# display.net
KiCad netlist of a schematic drawn in Altium Designer
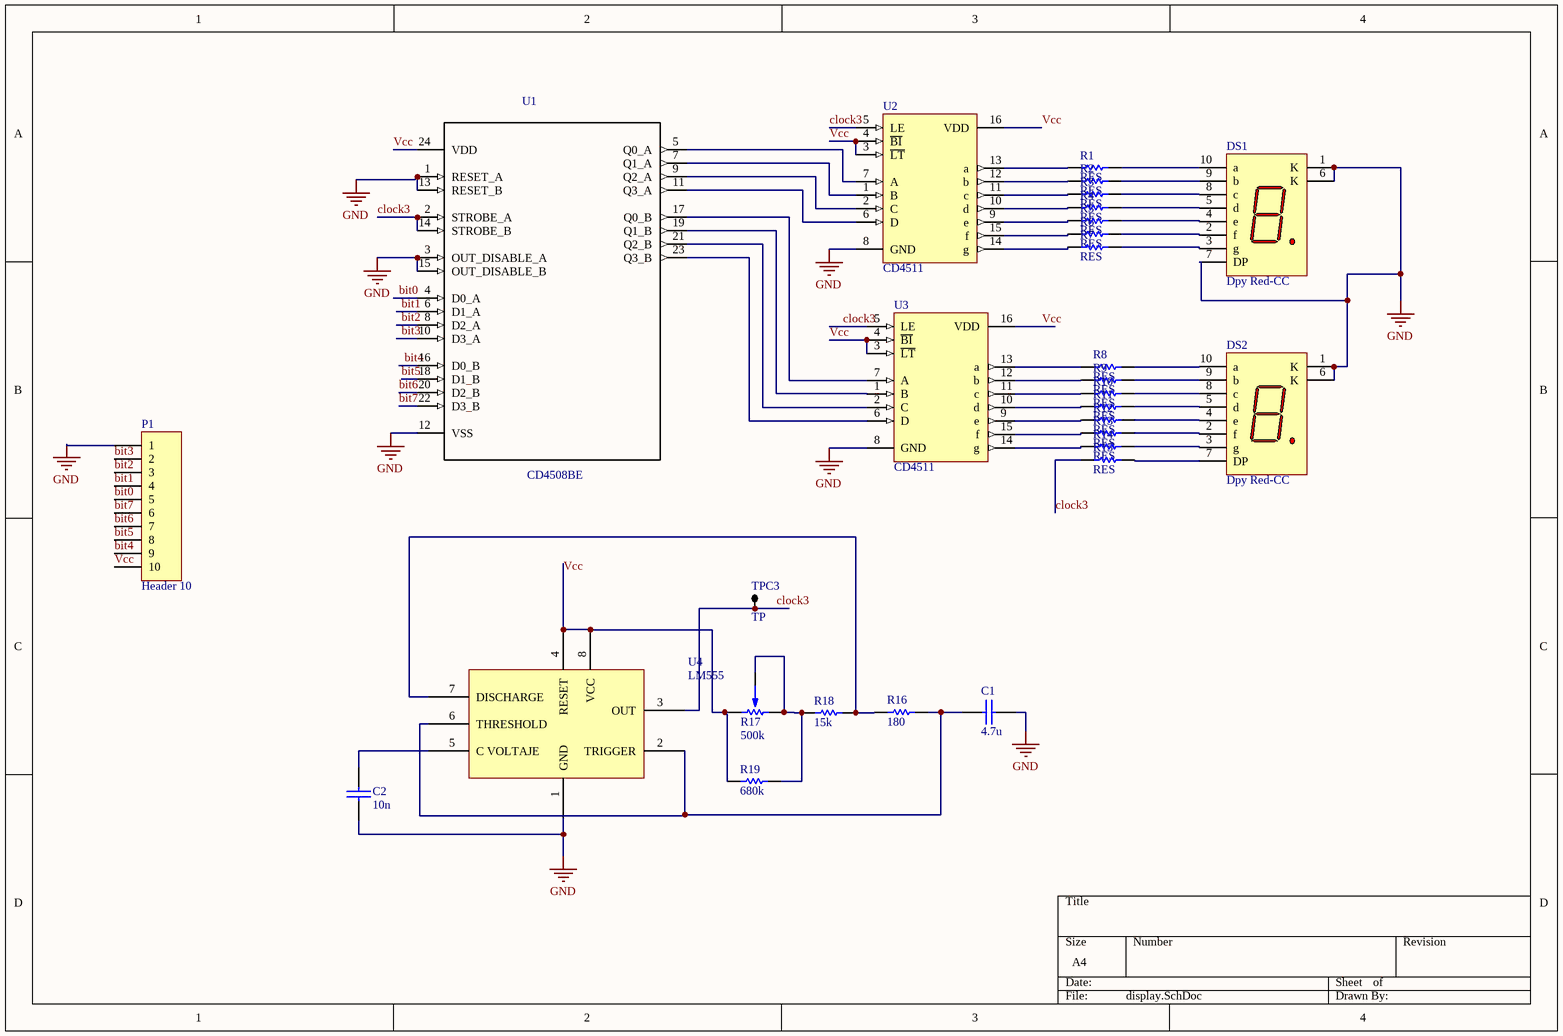
[diagram p0: display.SchDoc]

(export (version "E")
  (design (tool "Eeschema 10.0.6"))
  (components
    (comp (ref "C1") (value "4.7u") (footprint "0805") (libsource (lib "LIBEBAL") (part "CAP")))
    (comp (ref "C2") (value "10n") (footprint "CAP200") (libsource (lib "LIBEBAL") (part "CAP")))
    (comp (ref "DS1")
      (value "Dpy Red-CC")
      (footprint "A")
      (description "7.62 mm Black Surface HER 7-Segment Display: CC, RH DP")
      (fields (field (name "PUBLISHER") "Altium Limited"))
      (libsource (lib "Miscellaneous Devices") (part "Dpy Red-CC"))
    )
    (comp (ref "DS2")
      (value "Dpy Red-CC")
      (footprint "A")
      (description "7.62 mm Black Surface HER 7-Segment Display: CC, RH DP")
      (fields (field (name "PUBLISHER") "Altium Limited"))
      (libsource (lib "Miscellaneous Devices") (part "Dpy Red-CC"))
    )
    (comp (ref "P1")
      (value "Header 10")
      (footprint "HDR1X10")
      (description "Header, 10-Pin")
      (fields (field (name "PUBLISHER") "Altium Limited"))
      (libsource (lib "Miscellaneous Connectors") (part "Header 10"))
    )
    (comp (ref "R1") (value "RES") (footprint "0805") (libsource (lib "LIBEBAL") (part "RES")))
    (comp (ref "R2") (value "RES") (footprint "0805") (libsource (lib "LIBEBAL") (part "RES")))
    (comp (ref "R3") (value "RES") (footprint "0805") (libsource (lib "LIBEBAL") (part "RES")))
    (comp (ref "R4") (value "RES") (footprint "0805") (libsource (lib "LIBEBAL") (part "RES")))
    (comp (ref "R5") (value "RES") (footprint "0805") (libsource (lib "LIBEBAL") (part "RES")))
    (comp (ref "R6") (value "RES") (footprint "0805") (libsource (lib "LIBEBAL") (part "RES")))
    (comp (ref "R7") (value "RES") (footprint "0805") (libsource (lib "LIBEBAL") (part "RES")))
    (comp (ref "R8") (value "RES") (footprint "0805") (libsource (lib "LIBEBAL") (part "RES")))
    (comp (ref "R9") (value "RES") (footprint "0805") (libsource (lib "LIBEBAL") (part "RES")))
    (comp (ref "R10") (value "RES") (footprint "0805") (libsource (lib "LIBEBAL") (part "RES")))
    (comp (ref "R11") (value "RES") (footprint "0805") (libsource (lib "LIBEBAL") (part "RES")))
    (comp (ref "R12") (value "RES") (footprint "0805") (libsource (lib "LIBEBAL") (part "RES")))
    (comp (ref "R13") (value "RES") (footprint "0805") (libsource (lib "LIBEBAL") (part "RES")))
    (comp (ref "R14") (value "RES") (footprint "0805") (libsource (lib "LIBEBAL") (part "RES")))
    (comp (ref "R15") (value "RES") (footprint "0805") (libsource (lib "LIBEBAL") (part "RES")))
    (comp (ref "R16") (value "180") (footprint "0805") (libsource (lib "LIBEBAL") (part "RES")))
    (comp (ref "R17")
      (value "500k")
      (footprint "POTENCIOMETRO")
      (libsource (lib "LIBEBAL") (part "POTENCIOMETRO"))
    )
    (comp (ref "R18") (value "15k") (footprint "0805") (libsource (lib "LIBEBAL") (part "RES")))
    (comp (ref "R19") (value "680k") (footprint "RES400") (libsource (lib "LIBEBAL") (part "RES")))
    (comp (ref "TPC3") (value "TP") (footprint "TPTH") (libsource (lib "LIBEBAL") (part "TP")))
    (comp (ref "U1")
      (value "CD4508BE")
      (footprint "*DIP254P1080X508-24")
      (description "Latch Transparent 3-ST 8-CH D-Type 24-Pin PDIP")
      (fields (field (name "MF") "Texas Instruments"))
      (libsource (lib "CD4508BE") (part "CD4508BE"))
    )
    (comp (ref "U2")
      (value "CD4511")
      (footprint "DIP16")
      (description "BCD to 7 SEGMENTOS")
      (libsource (lib "LIBEBAL") (part "CD4511"))
    )
    (comp (ref "U3")
      (value "CD4511")
      (footprint "DIP16")
      (description "BCD to 7 SEGMENTOS")
      (libsource (lib "LIBEBAL") (part "CD4511"))
    )
    (comp (ref "U4")
      (value "LM555")
      (footprint "DIP8")
      (description "Timer")
      (libsource (lib "LIBEBAL") (part "LM555"))
    )
  )
  (nets
    (net (code "1") (name "/Vcc") (class "Default")
      (node (ref "P1") (pin "10") (pinfunction "10_10") (pintype "passive"))
      (node (ref "R17") (pin "1") (pinfunction "1_1") (pintype "passive"))
      (node (ref "R19") (pin "1") (pinfunction "1_1") (pintype "passive"))
      (node (ref "U1") (pin "24") (pinfunction "VDD_24") (pintype "power_in"))
      (node (ref "U2") (pin "16") (pinfunction "VDD_16") (pintype "power_in"))
      (node (ref "U2") (pin "3") (pinfunction "~{LT}_3") (pintype "input"))
      (node (ref "U2") (pin "4") (pinfunction "~{BI}_4") (pintype "input"))
      (node (ref "U3") (pin "16") (pinfunction "VDD_16") (pintype "power_in"))
      (node (ref "U3") (pin "3") (pinfunction "~{LT}_3") (pintype "input"))
      (node (ref "U3") (pin "4") (pinfunction "~{BI}_4") (pintype "input"))
      (node (ref "U4") (pin "4") (pinfunction "RESET_4") (pintype "passive"))
      (node (ref "U4") (pin "8") (pinfunction "VCC_8") (pintype "passive"))
    )
    (net (code "2") (name "/bit0") (class "Default")
      (node (ref "P1") (pin "5") (pinfunction "5_5") (pintype "passive"))
      (node (ref "U1") (pin "4") (pinfunction "D0_A_4") (pintype "input"))
    )
    (net (code "3") (name "/bit1") (class "Default")
      (node (ref "P1") (pin "4") (pinfunction "4_4") (pintype "passive"))
      (node (ref "U1") (pin "6") (pinfunction "D1_A_6") (pintype "input"))
    )
    (net (code "4") (name "/bit2") (class "Default")
      (node (ref "P1") (pin "3") (pinfunction "3_3") (pintype "passive"))
      (node (ref "U1") (pin "8") (pinfunction "D2_A_8") (pintype "input"))
    )
    (net (code "5") (name "/bit3") (class "Default")
      (node (ref "P1") (pin "2") (pinfunction "2_2") (pintype "passive"))
      (node (ref "U1") (pin "10") (pinfunction "D3_A_10") (pintype "input"))
    )
    (net (code "6") (name "/bit4") (class "Default")
      (node (ref "P1") (pin "9") (pinfunction "9_9") (pintype "passive"))
      (node (ref "U1") (pin "16") (pinfunction "D0_B_16") (pintype "input"))
    )
    (net (code "7") (name "/bit5") (class "Default")
      (node (ref "P1") (pin "8") (pinfunction "8_8") (pintype "passive"))
      (node (ref "U1") (pin "18") (pinfunction "D1_B_18") (pintype "input"))
    )
    (net (code "8") (name "/bit6") (class "Default")
      (node (ref "P1") (pin "7") (pinfunction "7_7") (pintype "passive"))
      (node (ref "U1") (pin "20") (pinfunction "D2_B_20") (pintype "input"))
    )
    (net (code "9") (name "/bit7") (class "Default")
      (node (ref "P1") (pin "6") (pinfunction "6_6") (pintype "passive"))
      (node (ref "U1") (pin "22") (pinfunction "D3_B_22") (pintype "input"))
    )
    (net (code "10") (name "/clock3") (class "Default")
      (node (ref "R15") (pin "1") (pinfunction "1_1") (pintype "passive"))
      (node (ref "TPC3") (pin "1") (pinfunction "1_1") (pintype "passive"))
      (node (ref "U1") (pin "14") (pinfunction "STROBE_B_14") (pintype "input"))
      (node (ref "U1") (pin "2") (pinfunction "STROBE_A_2") (pintype "input"))
      (node (ref "U2") (pin "5") (pinfunction "LE_5") (pintype "input"))
      (node (ref "U3") (pin "5") (pinfunction "LE_5") (pintype "input"))
      (node (ref "U4") (pin "3") (pinfunction "OUT_3") (pintype "passive"))
    )
    (net (code "11") (name "GND") (class "Default")
      (node (ref "C1") (pin "2") (pinfunction "2_2") (pintype "passive"))
      (node (ref "C2") (pin "1") (pinfunction "1_1") (pintype "passive"))
      (node (ref "DS1") (pin "1") (pinfunction "K_1") (pintype "passive"))
      (node (ref "DS1") (pin "6") (pinfunction "K_6") (pintype "passive"))
      (node (ref "DS1") (pin "7") (pinfunction "DP_7") (pintype "passive"))
      (node (ref "DS2") (pin "1") (pinfunction "K_1") (pintype "passive"))
      (node (ref "DS2") (pin "6") (pinfunction "K_6") (pintype "passive"))
      (node (ref "P1") (pin "1") (pinfunction "1_1") (pintype "passive"))
      (node (ref "U1") (pin "1") (pinfunction "RESET_A_1") (pintype "input"))
      (node (ref "U1") (pin "12") (pinfunction "VSS_12") (pintype "power_in"))
      (node (ref "U1") (pin "13") (pinfunction "RESET_B_13") (pintype "input"))
      (node (ref "U1") (pin "15") (pinfunction "OUT_DISABLE_B_15") (pintype "input"))
      (node (ref "U1") (pin "3") (pinfunction "OUT_DISABLE_A_3") (pintype "input"))
      (node (ref "U2") (pin "8") (pinfunction "GND_8") (pintype "power_in"))
      (node (ref "U3") (pin "8") (pinfunction "GND_8") (pintype "power_in"))
      (node (ref "U4") (pin "1") (pinfunction "GND_1") (pintype "passive"))
    )
    (net (code "12") (name "Net-(DS1-a)") (class "Default")
      (node (ref "DS1") (pin "10") (pinfunction "a_10") (pintype "passive"))
      (node (ref "R1") (pin "2") (pinfunction "2_2") (pintype "passive"))
    )
    (net (code "13") (name "Net-(DS1-b)") (class "Default")
      (node (ref "DS1") (pin "9") (pinfunction "b_9") (pintype "passive"))
      (node (ref "R2") (pin "2") (pinfunction "2_2") (pintype "passive"))
    )
    (net (code "14") (name "Net-(DS1-c)") (class "Default")
      (node (ref "DS1") (pin "8") (pinfunction "c_8") (pintype "passive"))
      (node (ref "R3") (pin "2") (pinfunction "2_2") (pintype "passive"))
    )
    (net (code "15") (name "Net-(DS1-d)") (class "Default")
      (node (ref "DS1") (pin "5") (pinfunction "d_5") (pintype "passive"))
      (node (ref "R4") (pin "2") (pinfunction "2_2") (pintype "passive"))
    )
    (net (code "16") (name "Net-(DS1-e)") (class "Default")
      (node (ref "DS1") (pin "4") (pinfunction "e_4") (pintype "passive"))
      (node (ref "R5") (pin "2") (pinfunction "2_2") (pintype "passive"))
    )
    (net (code "17") (name "Net-(DS1-f)") (class "Default")
      (node (ref "DS1") (pin "2") (pinfunction "f_2") (pintype "passive"))
      (node (ref "R6") (pin "2") (pinfunction "2_2") (pintype "passive"))
    )
    (net (code "18") (name "Net-(DS1-g)") (class "Default")
      (node (ref "DS1") (pin "3") (pinfunction "g_3") (pintype "passive"))
      (node (ref "R7") (pin "2") (pinfunction "2_2") (pintype "passive"))
    )
    (net (code "19") (name "Net-(DS2-DP)") (class "Default")
      (node (ref "DS2") (pin "7") (pinfunction "DP_7") (pintype "passive"))
      (node (ref "R15") (pin "2") (pinfunction "2_2") (pintype "passive"))
    )
    (net (code "20") (name "Net-(DS2-a)") (class "Default")
      (node (ref "DS2") (pin "10") (pinfunction "a_10") (pintype "passive"))
      (node (ref "R8") (pin "2") (pinfunction "2_2") (pintype "passive"))
    )
    (net (code "21") (name "Net-(DS2-b)") (class "Default")
      (node (ref "DS2") (pin "9") (pinfunction "b_9") (pintype "passive"))
      (node (ref "R9") (pin "2") (pinfunction "2_2") (pintype "passive"))
    )
    (net (code "22") (name "Net-(DS2-c)") (class "Default")
      (node (ref "DS2") (pin "8") (pinfunction "c_8") (pintype "passive"))
      (node (ref "R10") (pin "2") (pinfunction "2_2") (pintype "passive"))
    )
    (net (code "23") (name "Net-(DS2-d)") (class "Default")
      (node (ref "DS2") (pin "5") (pinfunction "d_5") (pintype "passive"))
      (node (ref "R11") (pin "2") (pinfunction "2_2") (pintype "passive"))
    )
    (net (code "24") (name "Net-(DS2-e)") (class "Default")
      (node (ref "DS2") (pin "4") (pinfunction "e_4") (pintype "passive"))
      (node (ref "R12") (pin "2") (pinfunction "2_2") (pintype "passive"))
    )
    (net (code "25") (name "Net-(DS2-f)") (class "Default")
      (node (ref "DS2") (pin "2") (pinfunction "f_2") (pintype "passive"))
      (node (ref "R13") (pin "2") (pinfunction "2_2") (pintype "passive"))
    )
    (net (code "26") (name "Net-(DS2-g)") (class "Default")
      (node (ref "DS2") (pin "3") (pinfunction "g_3") (pintype "passive"))
      (node (ref "R14") (pin "2") (pinfunction "2_2") (pintype "passive"))
    )
    (net (code "27") (name "Net-(R17-Pad2)") (class "Default")
      (node (ref "R17") (pin "2") (pinfunction "2_2") (pintype "passive"))
      (node (ref "R17") (pin "3") (pinfunction "3_3") (pintype "passive"))
      (node (ref "R18") (pin "1") (pinfunction "1_1") (pintype "passive"))
      (node (ref "R19") (pin "2") (pinfunction "2_2") (pintype "passive"))
    )
    (net (code "28") (name "Net-(U1-Q0_A)") (class "Default")
      (node (ref "U1") (pin "5") (pinfunction "Q0_A_5") (pintype "output"))
      (node (ref "U2") (pin "7") (pinfunction "A_7") (pintype "input"))
    )
    (net (code "29") (name "Net-(U1-Q0_B)") (class "Default")
      (node (ref "U1") (pin "17") (pinfunction "Q0_B_17") (pintype "output"))
      (node (ref "U3") (pin "7") (pinfunction "A_7") (pintype "input"))
    )
    (net (code "30") (name "Net-(U1-Q1_A)") (class "Default")
      (node (ref "U1") (pin "7") (pinfunction "Q1_A_7") (pintype "output"))
      (node (ref "U2") (pin "1") (pinfunction "B_1") (pintype "input"))
    )
    (net (code "31") (name "Net-(U1-Q1_B)") (class "Default")
      (node (ref "U1") (pin "19") (pinfunction "Q1_B_19") (pintype "output"))
      (node (ref "U3") (pin "1") (pinfunction "B_1") (pintype "input"))
    )
    (net (code "32") (name "Net-(U1-Q2_A)") (class "Default")
      (node (ref "U1") (pin "9") (pinfunction "Q2_A_9") (pintype "output"))
      (node (ref "U2") (pin "2") (pinfunction "C_2") (pintype "input"))
    )
    (net (code "33") (name "Net-(U1-Q2_B)") (class "Default")
      (node (ref "U1") (pin "21") (pinfunction "Q2_B_21") (pintype "output"))
      (node (ref "U3") (pin "2") (pinfunction "C_2") (pintype "input"))
    )
    (net (code "34") (name "Net-(U1-Q3_A)") (class "Default")
      (node (ref "U1") (pin "11") (pinfunction "Q3_A_11") (pintype "output"))
      (node (ref "U2") (pin "6") (pinfunction "D_6") (pintype "input"))
    )
    (net (code "35") (name "Net-(U1-Q3_B)") (class "Default")
      (node (ref "U1") (pin "23") (pinfunction "Q3_B_23") (pintype "output"))
      (node (ref "U3") (pin "6") (pinfunction "D_6") (pintype "input"))
    )
    (net (code "36") (name "Net-(U2-a)") (class "Default")
      (node (ref "R1") (pin "1") (pinfunction "1_1") (pintype "passive"))
      (node (ref "U2") (pin "13") (pinfunction "a_13") (pintype "output"))
    )
    (net (code "37") (name "Net-(U2-b)") (class "Default")
      (node (ref "R2") (pin "1") (pinfunction "1_1") (pintype "passive"))
      (node (ref "U2") (pin "12") (pinfunction "b_12") (pintype "output"))
    )
    (net (code "38") (name "Net-(U2-c)") (class "Default")
      (node (ref "R3") (pin "1") (pinfunction "1_1") (pintype "passive"))
      (node (ref "U2") (pin "11") (pinfunction "c_11") (pintype "output"))
    )
    (net (code "39") (name "Net-(U2-d)") (class "Default")
      (node (ref "R4") (pin "1") (pinfunction "1_1") (pintype "passive"))
      (node (ref "U2") (pin "10") (pinfunction "d_10") (pintype "output"))
    )
    (net (code "40") (name "Net-(U2-e)") (class "Default")
      (node (ref "R5") (pin "1") (pinfunction "1_1") (pintype "passive"))
      (node (ref "U2") (pin "9") (pinfunction "e_9") (pintype "output"))
    )
    (net (code "41") (name "Net-(U2-f)") (class "Default")
      (node (ref "R6") (pin "1") (pinfunction "1_1") (pintype "passive"))
      (node (ref "U2") (pin "15") (pinfunction "f_15") (pintype "output"))
    )
    (net (code "42") (name "Net-(U2-g)") (class "Default")
      (node (ref "R7") (pin "1") (pinfunction "1_1") (pintype "passive"))
      (node (ref "U2") (pin "14") (pinfunction "g_14") (pintype "output"))
    )
    (net (code "43") (name "Net-(U3-a)") (class "Default")
      (node (ref "R8") (pin "1") (pinfunction "1_1") (pintype "passive"))
      (node (ref "U3") (pin "13") (pinfunction "a_13") (pintype "output"))
    )
    (net (code "44") (name "Net-(U3-b)") (class "Default")
      (node (ref "R9") (pin "1") (pinfunction "1_1") (pintype "passive"))
      (node (ref "U3") (pin "12") (pinfunction "b_12") (pintype "output"))
    )
    (net (code "45") (name "Net-(U3-c)") (class "Default")
      (node (ref "R10") (pin "1") (pinfunction "1_1") (pintype "passive"))
      (node (ref "U3") (pin "11") (pinfunction "c_11") (pintype "output"))
    )
    (net (code "46") (name "Net-(U3-d)") (class "Default")
      (node (ref "R11") (pin "1") (pinfunction "1_1") (pintype "passive"))
      (node (ref "U3") (pin "10") (pinfunction "d_10") (pintype "output"))
    )
    (net (code "47") (name "Net-(U3-e)") (class "Default")
      (node (ref "R12") (pin "1") (pinfunction "1_1") (pintype "passive"))
      (node (ref "U3") (pin "9") (pinfunction "e_9") (pintype "output"))
    )
    (net (code "48") (name "Net-(U3-f)") (class "Default")
      (node (ref "R13") (pin "1") (pinfunction "1_1") (pintype "passive"))
      (node (ref "U3") (pin "15") (pinfunction "f_15") (pintype "output"))
    )
    (net (code "49") (name "Net-(U3-g)") (class "Default")
      (node (ref "R14") (pin "1") (pinfunction "1_1") (pintype "passive"))
      (node (ref "U3") (pin "14") (pinfunction "g_14") (pintype "output"))
    )
    (net (code "50") (name "Net-(U4-C_VOLTAJE)") (class "Default")
      (node (ref "C2") (pin "2") (pinfunction "2_2") (pintype "passive"))
      (node (ref "U4") (pin "5") (pinfunction "C_VOLTAJE_5") (pintype "passive"))
    )
    (net (code "51") (name "Net-(U4-DISCHARGE)") (class "Default")
      (node (ref "R16") (pin "1") (pinfunction "1_1") (pintype "passive"))
      (node (ref "R18") (pin "2") (pinfunction "2_2") (pintype "passive"))
      (node (ref "U4") (pin "7") (pinfunction "DISCHARGE_7") (pintype "passive"))
    )
    (net (code "52") (name "Net-(U4-THRESHOLD)") (class "Default")
      (node (ref "C1") (pin "1") (pinfunction "1_1") (pintype "passive"))
      (node (ref "R16") (pin "2") (pinfunction "2_2") (pintype "passive"))
      (node (ref "U4") (pin "2") (pinfunction "TRIGGER_2") (pintype "passive"))
      (node (ref "U4") (pin "6") (pinfunction "THRESHOLD_6") (pintype "passive"))
    )
  )
)
